# clockv2.net
KiCad netlist of a schematic drawn in EAGLE
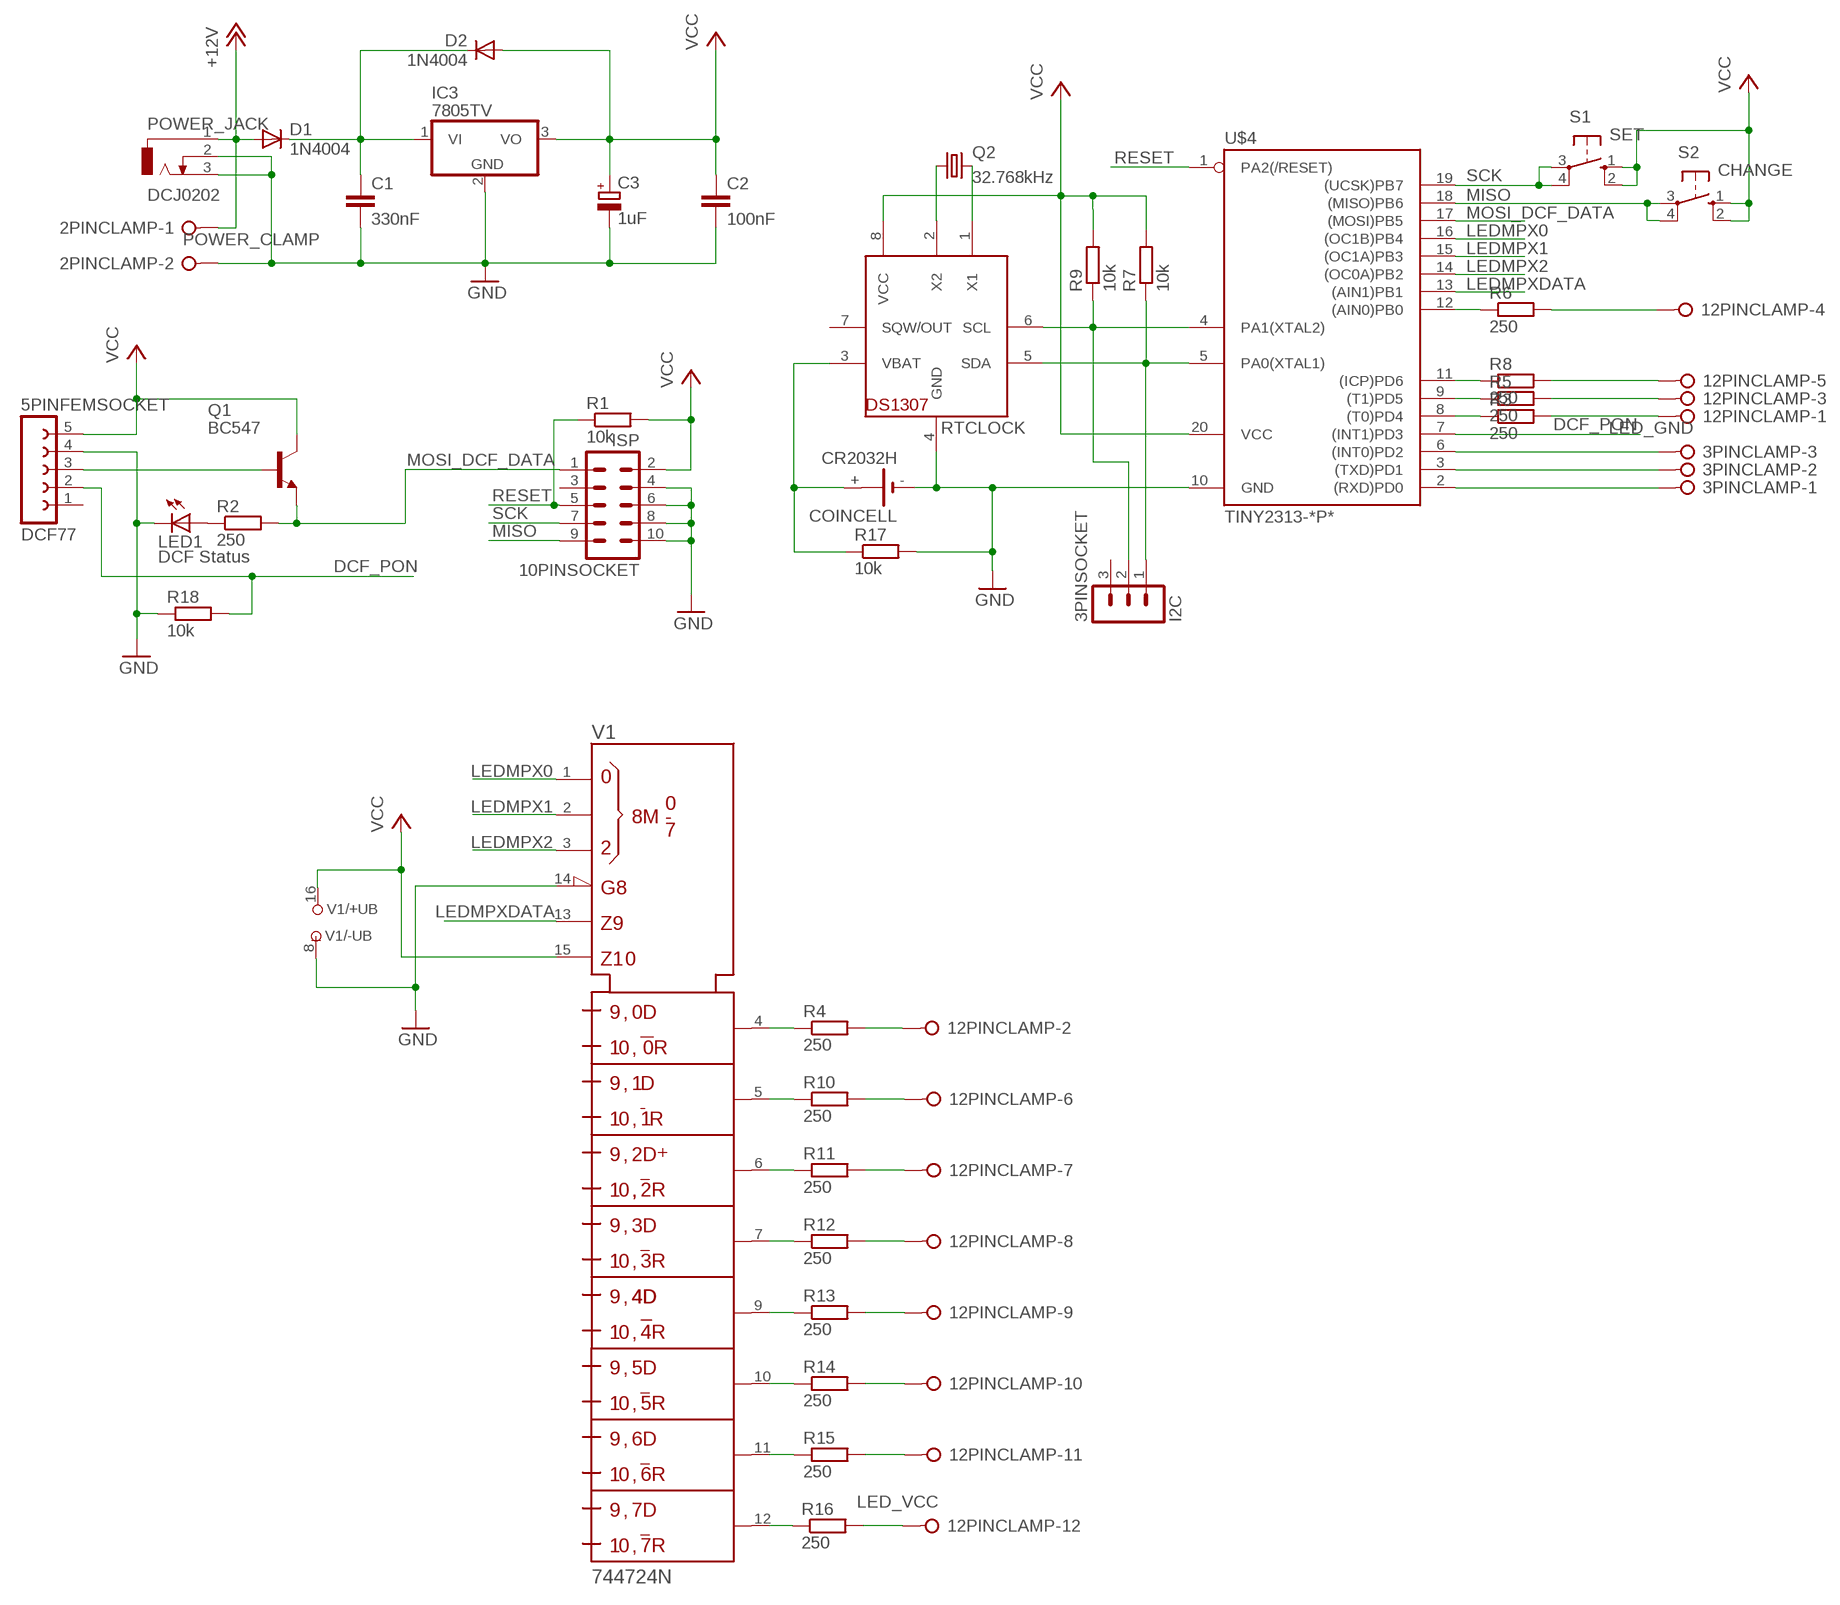
[diagram p0: schematic, sheet 1]

(export (version "E")
  (design (tool "Eeschema 10.0.6"))
  (components
    (comp (ref "2PINCLAMP")
      (value "POWER_CLAMP")
      (footprint "eagle-import:W237-132")
      (libsource (lib "eagle-import") (part "W237-02P"))
    )
    (comp (ref "3PINCLAMP")
      (value "LED_GND")
      (footprint "eagle-import:W237-133")
      (libsource (lib "eagle-import") (part "W237-03P"))
    )
    (comp (ref "3PINSOCKET")
      (value "I2C")
      (footprint "eagle-import:MA03-1")
      (libsource (lib "eagle-import") (part "MA03-1"))
    )
    (comp (ref "5PINFEMSOCKET")
      (value "DCF77")
      (footprint "eagle-import:FE05-1")
      (libsource (lib "eagle-import") (part "FE05-1"))
    )
    (comp (ref "10PINSOCKET")
      (value "ISP")
      (footprint "eagle-import:ML10")
      (libsource (lib "eagle-import") (part "ML10"))
    )
    (comp (ref "12PINCLAMP")
      (value "LED_VCC")
      (footprint "eagle-import:W237-12P")
      (libsource (lib "eagle-import") (part "W237-12P"))
    )
    (comp (ref "C1")
      (value "330nF")
      (footprint "eagle-import:C050-025X075")
      (libsource (lib "eagle-import") (part "C-EU050-025X075"))
    )
    (comp (ref "C2")
      (value "100nF")
      (footprint "eagle-import:C050-025X075")
      (libsource (lib "eagle-import") (part "C-EU050-025X075"))
    )
    (comp (ref "C3")
      (value "1uF")
      (footprint "eagle-import:E2-4")
      (libsource (lib "eagle-import") (part "CPOL-EUE2-4"))
    )
    (comp (ref "COINCELL")
      (value "CR2032H")
      (footprint "eagle-import:CR2032H")
      (libsource (lib "eagle-import") (part "CR2032H"))
    )
    (comp (ref "D1")
      (value "1N4004")
      (footprint "eagle-import:DO41-10")
      (libsource (lib "eagle-import") (part "1N4004"))
    )
    (comp (ref "D2")
      (value "1N4004")
      (footprint "eagle-import:DO41-10")
      (libsource (lib "eagle-import") (part "1N4004"))
    )
    (comp (ref "IC3")
      (value "7805TV")
      (footprint "eagle-import:TO220V")
      (libsource (lib "eagle-import") (part "78TV05"))
    )
    (comp (ref "LED1")
      (value "DCF Status")
      (footprint "eagle-import:LED5MM")
      (libsource (lib "eagle-import") (part "LED5MM"))
    )
    (comp (ref "POWER_JACK")
      (value "DCJ0202")
      (footprint "eagle-import:DCJ0202")
      (libsource (lib "eagle-import") (part "DCJ0202"))
    )
    (comp (ref "Q1")
      (value "BC547")
      (footprint "eagle-import:TO92")
      (libsource (lib "eagle-import") (part "BC547"))
    )
    (comp (ref "Q2")
      (value "32.768kHz")
      (footprint "eagle-import:TC38H")
      (libsource (lib "eagle-import") (part "CRYSTALTC38H"))
    )
    (comp (ref "R1")
      (value "10k")
      (footprint "eagle-import:0204_5")
      (libsource (lib "eagle-import") (part "R-EU_0204/5"))
    )
    (comp (ref "R2")
      (value "250")
      (footprint "eagle-import:0204_5")
      (libsource (lib "eagle-import") (part "R-EU_0204/5"))
    )
    (comp (ref "R3")
      (value "250")
      (footprint "eagle-import:0204_5")
      (libsource (lib "eagle-import") (part "R-EU_0204/5"))
    )
    (comp (ref "R4")
      (value "250")
      (footprint "eagle-import:0204_5")
      (libsource (lib "eagle-import") (part "R-EU_0204/5"))
    )
    (comp (ref "R5")
      (value "250")
      (footprint "eagle-import:0204_5")
      (libsource (lib "eagle-import") (part "R-EU_0204/5"))
    )
    (comp (ref "R6")
      (value "250")
      (footprint "eagle-import:0204_5")
      (libsource (lib "eagle-import") (part "R-EU_0204/5"))
    )
    (comp (ref "R7")
      (value "10k")
      (footprint "eagle-import:0204_5")
      (libsource (lib "eagle-import") (part "R-EU_0204/5"))
    )
    (comp (ref "R8")
      (value "250")
      (footprint "eagle-import:0204_5")
      (libsource (lib "eagle-import") (part "R-EU_0204/5"))
    )
    (comp (ref "R9")
      (value "10k")
      (footprint "eagle-import:0204_5")
      (libsource (lib "eagle-import") (part "R-EU_0204/5"))
    )
    (comp (ref "R10")
      (value "250")
      (footprint "eagle-import:0204_5")
      (libsource (lib "eagle-import") (part "R-EU_0204/5"))
    )
    (comp (ref "R11")
      (value "250")
      (footprint "eagle-import:0204_5")
      (libsource (lib "eagle-import") (part "R-EU_0204/5"))
    )
    (comp (ref "R12")
      (value "250")
      (footprint "eagle-import:0204_5")
      (libsource (lib "eagle-import") (part "R-EU_0204/5"))
    )
    (comp (ref "R13")
      (value "250")
      (footprint "eagle-import:0204_5")
      (libsource (lib "eagle-import") (part "R-EU_0204/5"))
    )
    (comp (ref "R14")
      (value "250")
      (footprint "eagle-import:0204_5")
      (libsource (lib "eagle-import") (part "R-EU_0204/5"))
    )
    (comp (ref "R15")
      (value "250")
      (footprint "eagle-import:0204_5")
      (libsource (lib "eagle-import") (part "R-EU_0204/5"))
    )
    (comp (ref "R16")
      (value "250")
      (footprint "eagle-import:0204_5")
      (libsource (lib "eagle-import") (part "R-EU_0204/5"))
    )
    (comp (ref "R17")
      (value "10k")
      (footprint "eagle-import:0204_5")
      (libsource (lib "eagle-import") (part "R-EU_0204/5"))
    )
    (comp (ref "R18")
      (value "10k")
      (footprint "eagle-import:0204_5")
      (libsource (lib "eagle-import") (part "R-EU_0204/5"))
    )
    (comp (ref "RTCLOCK")
      (value "DS1307")
      (footprint "eagle-import:DIL08")
      (libsource (lib "eagle-import") (part "DS1307"))
    )
    (comp (ref "S1")
      (value "SET")
      (footprint "eagle-import:B3F-10XX")
      (fields (field (name "MPN") "B3F-1000"))
      (libsource (lib "eagle-import") (part "10-XX"))
    )
    (comp (ref "S2")
      (value "CHANGE")
      (footprint "eagle-import:B3F-10XX")
      (fields (field (name "MPN") "B3F-1000"))
      (libsource (lib "eagle-import") (part "10-XX"))
    )
    (comp (ref "U$4")
      (value "TINY2313-*P*")
      (footprint "eagle-import:DIL20")
      (libsource (lib "eagle-import") (part "TINY2313-P"))
    )
    (comp (ref "V1")
      (value "744724N")
      (footprint "eagle-import:DIL16")
      (libsource (lib "eagle-import") (part "744724N"))
    )
  )
  (nets
    (net (code "1") (name "+12V") (class "Default")
      (node (ref "2PINCLAMP") (pin "1") (pinfunction "KL_1") (pintype "passive"))
      (node (ref "D1") (pin "A") (pinfunction "A_A") (pintype "passive"))
      (node (ref "POWER_JACK") (pin "1") (pinfunction "1_1") (pintype "passive"))
    )
    (net (code "2") (name "/DCF_PON") (class "Default")
      (node (ref "5PINFEMSOCKET") (pin "2") (pinfunction "2_2") (pintype "passive"))
      (node (ref "R18") (pin "2") (pinfunction "2_2") (pintype "passive"))
      (node (ref "U$4") (pin "7") (pinfunction "(INT1)PD3_7") (pintype "bidirectional"))
    )
    (net (code "3") (name "/LEDMPX0") (class "Default")
      (node (ref "U$4") (pin "16") (pinfunction "(OC1B)PB4_16") (pintype "bidirectional"))
      (node (ref "V1") (pin "1") (pinfunction "S0_1") (pintype "input"))
    )
    (net (code "4") (name "/LEDMPX1") (class "Default")
      (node (ref "U$4") (pin "15") (pinfunction "(OC1A)PB3_15") (pintype "bidirectional"))
      (node (ref "V1") (pin "2") (pinfunction "S1_2") (pintype "input"))
    )
    (net (code "5") (name "/LEDMPX2") (class "Default")
      (node (ref "U$4") (pin "14") (pinfunction "(OC0A)PB2_14") (pintype "bidirectional"))
      (node (ref "V1") (pin "3") (pinfunction "S2_3") (pintype "input"))
    )
    (net (code "6") (name "/LEDMPXDATA") (class "Default")
      (node (ref "U$4") (pin "13") (pinfunction "(AIN1)PB1_13") (pintype "bidirectional"))
      (node (ref "V1") (pin "13") (pinfunction "D_13") (pintype "input"))
    )
    (net (code "7") (name "/MISO") (class "Default")
      (node (ref "10PINSOCKET") (pin "9") (pinfunction "9_9") (pintype "passive"))
      (node (ref "S2") (pin "3") (pinfunction "P_3") (pintype "passive"))
      (node (ref "S2") (pin "4") (pinfunction "P1_4") (pintype "passive"))
      (node (ref "U$4") (pin "18") (pinfunction "(MISO)PB6_18") (pintype "bidirectional"))
    )
    (net (code "8") (name "/MOSI_DCF_DATA") (class "Default")
      (node (ref "10PINSOCKET") (pin "1") (pinfunction "1_1") (pintype "passive"))
      (node (ref "Q1") (pin "1") (pinfunction "E_1") (pintype "passive"))
      (node (ref "R2") (pin "2") (pinfunction "2_2") (pintype "passive"))
      (node (ref "U$4") (pin "17") (pinfunction "(MOSI)PB5_17") (pintype "bidirectional"))
    )
    (net (code "9") (name "/RESET") (class "Default")
      (node (ref "10PINSOCKET") (pin "5") (pinfunction "5_5") (pintype "passive"))
      (node (ref "R1") (pin "1") (pinfunction "1_1") (pintype "passive"))
      (node (ref "U$4") (pin "1") (pinfunction "PA2(/RESET)_1") (pintype "input"))
    )
    (net (code "10") (name "/SCK") (class "Default")
      (node (ref "10PINSOCKET") (pin "7") (pinfunction "7_7") (pintype "passive"))
      (node (ref "S1") (pin "3") (pinfunction "P_3") (pintype "passive"))
      (node (ref "S1") (pin "4") (pinfunction "P1_4") (pintype "passive"))
      (node (ref "U$4") (pin "19") (pinfunction "(UCSK)PB7_19") (pintype "bidirectional"))
    )
    (net (code "11") (name "GND") (class "Default")
      (node (ref "10PINSOCKET") (pin "10") (pinfunction "10_10") (pintype "passive"))
      (node (ref "10PINSOCKET") (pin "4") (pinfunction "4_4") (pintype "passive"))
      (node (ref "10PINSOCKET") (pin "6") (pinfunction "6_6") (pintype "passive"))
      (node (ref "10PINSOCKET") (pin "8") (pinfunction "8_8") (pintype "passive"))
      (node (ref "2PINCLAMP") (pin "2") (pinfunction "KL_2") (pintype "passive"))
      (node (ref "5PINFEMSOCKET") (pin "4") (pinfunction "4_4") (pintype "passive"))
      (node (ref "C1") (pin "2") (pinfunction "2_2") (pintype "passive"))
      (node (ref "C2") (pin "2") (pinfunction "2_2") (pintype "passive"))
      (node (ref "C3") (pin "-") (pinfunction "-_-") (pintype "passive"))
      (node (ref "COINCELL") (pin "-") (pinfunction "-_-") (pintype "passive"))
      (node (ref "IC3") (pin "2") (pinfunction "GND_2") (pintype "passive"))
      (node (ref "LED1") (pin "K") (pinfunction "C_K") (pintype "passive"))
      (node (ref "POWER_JACK") (pin "2") (pinfunction "2_2") (pintype "passive"))
      (node (ref "POWER_JACK") (pin "3") (pinfunction "3_3") (pintype "passive"))
      (node (ref "R17") (pin "2") (pinfunction "2_2") (pintype "passive"))
      (node (ref "R18") (pin "1") (pinfunction "1_1") (pintype "passive"))
      (node (ref "RTCLOCK") (pin "4") (pinfunction "GND_4") (pintype "power_in"))
      (node (ref "U$4") (pin "10") (pinfunction "GND_10") (pintype "power_in"))
      (node (ref "V1") (pin "14") (pinfunction "~{G}_14") (pintype "input"))
      (node (ref "V1") (pin "8") (pinfunction "-UB_8") (pintype "power_in"))
    )
    (net (code "12") (name "Net-(3PINCLAMPA-KL)") (class "Default")
      (node (ref "3PINCLAMP") (pin "1") (pinfunction "KL_1") (pintype "passive"))
      (node (ref "U$4") (pin "2") (pinfunction "(RXD)PD0_2") (pintype "bidirectional"))
    )
    (net (code "13") (name "Net-(3PINCLAMPB-KL)") (class "Default")
      (node (ref "3PINCLAMP") (pin "2") (pinfunction "KL_2") (pintype "passive"))
      (node (ref "U$4") (pin "3") (pinfunction "(TXD)PD1_3") (pintype "bidirectional"))
    )
    (net (code "14") (name "Net-(3PINCLAMPC-KL)") (class "Default")
      (node (ref "3PINCLAMP") (pin "3") (pinfunction "KL_3") (pintype "passive"))
      (node (ref "U$4") (pin "6") (pinfunction "(INT0)PD2_6") (pintype "bidirectional"))
    )
    (net (code "15") (name "Net-(12PINCLAMPA-KL)") (class "Default")
      (node (ref "12PINCLAMP") (pin "1") (pinfunction "KL_1") (pintype "passive"))
      (node (ref "R3") (pin "2") (pinfunction "2_2") (pintype "passive"))
    )
    (net (code "16") (name "Net-(12PINCLAMPB-KL)") (class "Default")
      (node (ref "12PINCLAMP") (pin "10") (pinfunction "KL_10") (pintype "passive"))
      (node (ref "R14") (pin "2") (pinfunction "2_2") (pintype "passive"))
    )
    (net (code "17") (name "Net-(12PINCLAMPC-KL)") (class "Default")
      (node (ref "12PINCLAMP") (pin "11") (pinfunction "KL_11") (pintype "passive"))
      (node (ref "R15") (pin "2") (pinfunction "2_2") (pintype "passive"))
    )
    (net (code "18") (name "Net-(12PINCLAMPD-KL)") (class "Default")
      (node (ref "12PINCLAMP") (pin "12") (pinfunction "KL_12") (pintype "passive"))
      (node (ref "R16") (pin "2") (pinfunction "2_2") (pintype "passive"))
    )
    (net (code "19") (name "Net-(12PINCLAMPE-KL)") (class "Default")
      (node (ref "12PINCLAMP") (pin "2") (pinfunction "KL_2") (pintype "passive"))
      (node (ref "R4") (pin "2") (pinfunction "2_2") (pintype "passive"))
    )
    (net (code "20") (name "Net-(12PINCLAMPF-KL)") (class "Default")
      (node (ref "12PINCLAMP") (pin "3") (pinfunction "KL_3") (pintype "passive"))
      (node (ref "R5") (pin "2") (pinfunction "2_2") (pintype "passive"))
    )
    (net (code "21") (name "Net-(12PINCLAMPG-KL)") (class "Default")
      (node (ref "12PINCLAMP") (pin "4") (pinfunction "KL_4") (pintype "passive"))
      (node (ref "R6") (pin "2") (pinfunction "2_2") (pintype "passive"))
    )
    (net (code "22") (name "Net-(12PINCLAMPH-KL)") (class "Default")
      (node (ref "12PINCLAMP") (pin "5") (pinfunction "KL_5") (pintype "passive"))
      (node (ref "R8") (pin "2") (pinfunction "2_2") (pintype "passive"))
    )
    (net (code "23") (name "Net-(12PINCLAMPI-KL)") (class "Default")
      (node (ref "12PINCLAMP") (pin "6") (pinfunction "KL_6") (pintype "passive"))
      (node (ref "R10") (pin "2") (pinfunction "2_2") (pintype "passive"))
    )
    (net (code "24") (name "Net-(12PINCLAMPJ-KL)") (class "Default")
      (node (ref "12PINCLAMP") (pin "7") (pinfunction "KL_7") (pintype "passive"))
      (node (ref "R11") (pin "2") (pinfunction "2_2") (pintype "passive"))
    )
    (net (code "25") (name "Net-(12PINCLAMPK-KL)") (class "Default")
      (node (ref "12PINCLAMP") (pin "8") (pinfunction "KL_8") (pintype "passive"))
      (node (ref "R12") (pin "2") (pinfunction "2_2") (pintype "passive"))
    )
    (net (code "26") (name "Net-(12PINCLAMPL-KL)") (class "Default")
      (node (ref "12PINCLAMP") (pin "9") (pinfunction "KL_9") (pintype "passive"))
      (node (ref "R13") (pin "2") (pinfunction "2_2") (pintype "passive"))
    )
    (net (code "27") (name "Net-(IC3-VI)") (class "Default")
      (node (ref "C1") (pin "1") (pinfunction "1_1") (pintype "passive"))
      (node (ref "D1") (pin "C") (pinfunction "C_C") (pintype "passive"))
      (node (ref "D2") (pin "C") (pinfunction "C_C") (pintype "passive"))
      (node (ref "IC3") (pin "1") (pinfunction "VI_1") (pintype "input"))
    )
    (net (code "28") (name "Net-(LED1-PadA)") (class "Default")
      (node (ref "LED1") (pin "A") (pinfunction "A_A") (pintype "passive"))
      (node (ref "R2") (pin "1") (pinfunction "1_1") (pintype "passive"))
    )
    (net (code "29") (name "Net-(Q1-B)") (class "Default")
      (node (ref "5PINFEMSOCKET") (pin "3") (pinfunction "3_3") (pintype "passive"))
      (node (ref "Q1") (pin "2") (pinfunction "B_2") (pintype "passive"))
    )
    (net (code "30") (name "Net-(RTCLOCK-SCL)") (class "Default")
      (node (ref "3PINSOCKET") (pin "2") (pinfunction "2_2") (pintype "passive"))
      (node (ref "R9") (pin "1") (pinfunction "1_1") (pintype "passive"))
      (node (ref "RTCLOCK") (pin "6") (pinfunction "SCL_6") (pintype "bidirectional"))
      (node (ref "U$4") (pin "4") (pinfunction "PA1(XTAL2)_4") (pintype "bidirectional"))
    )
    (net (code "31") (name "Net-(RTCLOCK-SDA)") (class "Default")
      (node (ref "3PINSOCKET") (pin "1") (pinfunction "1_1") (pintype "passive"))
      (node (ref "R7") (pin "1") (pinfunction "1_1") (pintype "passive"))
      (node (ref "RTCLOCK") (pin "5") (pinfunction "SDA_5") (pintype "bidirectional"))
      (node (ref "U$4") (pin "5") (pinfunction "PA0(XTAL1)_5") (pintype "bidirectional"))
    )
    (net (code "32") (name "Net-(RTCLOCK-VBAT)") (class "Default")
      (node (ref "COINCELL") (pin "+") (pinfunction "+_+") (pintype "passive"))
      (node (ref "R17") (pin "1") (pinfunction "1_1") (pintype "passive"))
      (node (ref "RTCLOCK") (pin "3") (pinfunction "VBAT_3") (pintype "power_in"))
    )
    (net (code "33") (name "Net-(RTCLOCK-X1)") (class "Default")
      (node (ref "Q2") (pin "2") (pinfunction "2_2") (pintype "passive"))
      (node (ref "RTCLOCK") (pin "1") (pinfunction "X1_1") (pintype "passive"))
    )
    (net (code "34") (name "Net-(RTCLOCK-X2)") (class "Default")
      (node (ref "Q2") (pin "1") (pinfunction "1_1") (pintype "passive"))
      (node (ref "RTCLOCK") (pin "2") (pinfunction "X2_2") (pintype "passive"))
    )
    (net (code "35") (name "Net-(U$4-(AIN0)PB0)") (class "Default")
      (node (ref "R6") (pin "1") (pinfunction "1_1") (pintype "passive"))
      (node (ref "U$4") (pin "12") (pinfunction "(AIN0)PB0_12") (pintype "bidirectional"))
    )
    (net (code "36") (name "Net-(U$4-(ICP)PD6)") (class "Default")
      (node (ref "R8") (pin "1") (pinfunction "1_1") (pintype "passive"))
      (node (ref "U$4") (pin "11") (pinfunction "(ICP)PD6_11") (pintype "bidirectional"))
    )
    (net (code "37") (name "Net-(U$4-(T0)PD4)") (class "Default")
      (node (ref "R3") (pin "1") (pinfunction "1_1") (pintype "passive"))
      (node (ref "U$4") (pin "8") (pinfunction "(T0)PD4_8") (pintype "bidirectional"))
    )
    (net (code "38") (name "Net-(U$4-(T1)PD5)") (class "Default")
      (node (ref "R5") (pin "1") (pinfunction "1_1") (pintype "passive"))
      (node (ref "U$4") (pin "9") (pinfunction "(T1)PD5_9") (pintype "bidirectional"))
    )
    (net (code "39") (name "Net-(V1C-Q0)") (class "Default")
      (node (ref "R4") (pin "1") (pinfunction "1_1") (pintype "passive"))
      (node (ref "V1") (pin "4") (pinfunction "Q0_4") (pintype "output"))
    )
    (net (code "40") (name "Net-(V1C-Q1)") (class "Default")
      (node (ref "R10") (pin "1") (pinfunction "1_1") (pintype "passive"))
      (node (ref "V1") (pin "5") (pinfunction "Q1_5") (pintype "output"))
    )
    (net (code "41") (name "Net-(V1C-Q2)") (class "Default")
      (node (ref "R11") (pin "1") (pinfunction "1_1") (pintype "passive"))
      (node (ref "V1") (pin "6") (pinfunction "Q2_6") (pintype "output"))
    )
    (net (code "42") (name "Net-(V1C-Q3)") (class "Default")
      (node (ref "R12") (pin "1") (pinfunction "1_1") (pintype "passive"))
      (node (ref "V1") (pin "7") (pinfunction "Q3_7") (pintype "output"))
    )
    (net (code "43") (name "Net-(V1C-Q4)") (class "Default")
      (node (ref "R13") (pin "1") (pinfunction "1_1") (pintype "passive"))
      (node (ref "V1") (pin "9") (pinfunction "Q4_9") (pintype "output"))
    )
    (net (code "44") (name "Net-(V1C-Q5)") (class "Default")
      (node (ref "R14") (pin "1") (pinfunction "1_1") (pintype "passive"))
      (node (ref "V1") (pin "10") (pinfunction "Q5_10") (pintype "output"))
    )
    (net (code "45") (name "Net-(V1C-Q6)") (class "Default")
      (node (ref "R15") (pin "1") (pinfunction "1_1") (pintype "passive"))
      (node (ref "V1") (pin "11") (pinfunction "Q6_11") (pintype "output"))
    )
    (net (code "46") (name "Net-(V1C-Q7)") (class "Default")
      (node (ref "R16") (pin "1") (pinfunction "1_1") (pintype "passive"))
      (node (ref "V1") (pin "12") (pinfunction "Q7_12") (pintype "output"))
    )
    (net (code "47") (name "VCC") (class "Default")
      (node (ref "10PINSOCKET") (pin "2") (pinfunction "2_2") (pintype "passive"))
      (node (ref "5PINFEMSOCKET") (pin "5") (pinfunction "5_5") (pintype "passive"))
      (node (ref "C2") (pin "1") (pinfunction "1_1") (pintype "passive"))
      (node (ref "C3") (pin "+") (pinfunction "+_+") (pintype "passive"))
      (node (ref "D2") (pin "A") (pinfunction "A_A") (pintype "passive"))
      (node (ref "IC3") (pin "3") (pinfunction "VO_3") (pintype "passive"))
      (node (ref "Q1") (pin "3") (pinfunction "C_3") (pintype "passive"))
      (node (ref "R1") (pin "2") (pinfunction "2_2") (pintype "passive"))
      (node (ref "R7") (pin "2") (pinfunction "2_2") (pintype "passive"))
      (node (ref "R9") (pin "2") (pinfunction "2_2") (pintype "passive"))
      (node (ref "RTCLOCK") (pin "8") (pinfunction "VCC_8") (pintype "power_in"))
      (node (ref "S1") (pin "1") (pinfunction "S_1") (pintype "passive"))
      (node (ref "S1") (pin "2") (pinfunction "S1_2") (pintype "passive"))
      (node (ref "S2") (pin "1") (pinfunction "S_1") (pintype "passive"))
      (node (ref "S2") (pin "2") (pinfunction "S1_2") (pintype "passive"))
      (node (ref "U$4") (pin "20") (pinfunction "VCC_20") (pintype "power_in"))
      (node (ref "V1") (pin "15") (pinfunction "CLR_15") (pintype "input"))
      (node (ref "V1") (pin "16") (pinfunction "+UB_16") (pintype "power_in"))
    )
    (net (code "48") (name "unconnected-(3PINSOCKET-Pad3)") (class "Default")
      (node (ref "3PINSOCKET") (pin "3") (pinfunction "3_3") (pintype "passive"))
    )
    (net (code "49") (name "unconnected-(5PINFEMSOCKET-Pad1)") (class "Default")
      (node (ref "5PINFEMSOCKET") (pin "1") (pinfunction "1_1") (pintype "passive"))
    )
    (net (code "50") (name "unconnected-(10PINSOCKET-Pad3)") (class "Default")
      (node (ref "10PINSOCKET") (pin "3") (pinfunction "3_3") (pintype "passive"))
    )
    (net (code "51") (name "unconnected-(COINCELL-+-Pad+@1)") (class "Default")
      (node (ref "COINCELL") (pin "+@1") (pinfunction "+_+@1") (pintype "passive"))
    )
    (net (code "52") (name "unconnected-(RTCLOCK-SQW{slash}OUT-Pad7)") (class "Default")
      (node (ref "RTCLOCK") (pin "7") (pinfunction "SQW/OUT_7") (pintype "bidirectional"))
    )
  )
)
